# daughter.net
KiCad netlist of a schematic drawn in Altium Designer
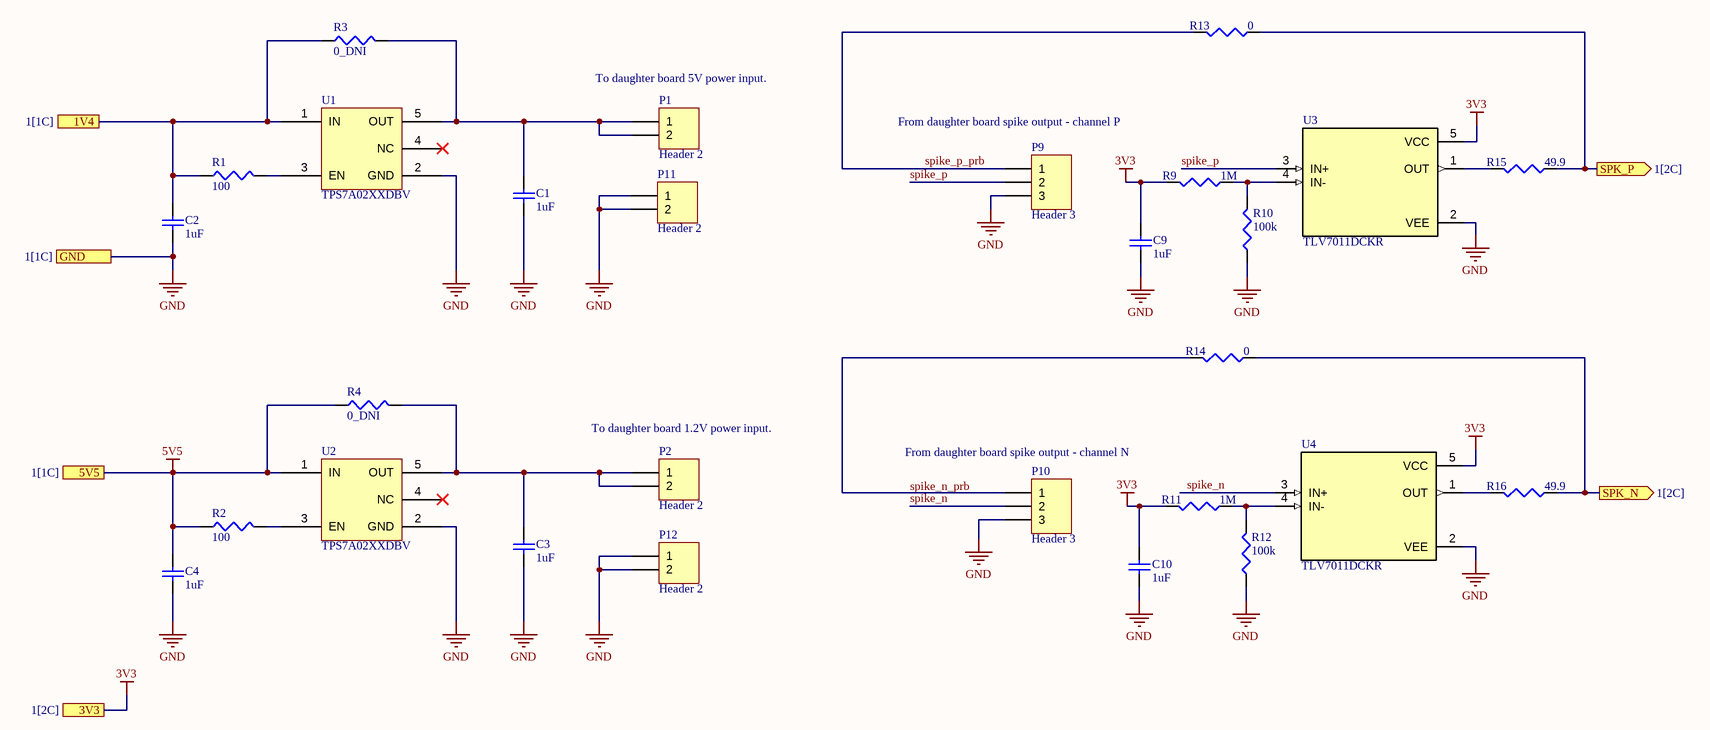
[diagram p0: daughter.SchDoc]

(export (version "E")
  (design (tool "Eeschema 10.0.6"))
  (components
    (comp (ref "C1")
      (value "1uF")
      (footprint "SMD-0603")
      (description "Ceramic Capacitor 0603")
      (libsource (lib "LCR") (part "CAP0603"))
    )
    (comp (ref "C2")
      (value "1uF")
      (footprint "SMD-0603")
      (description "Ceramic Capacitor 0603")
      (libsource (lib "LCR") (part "CAP0603"))
    )
    (comp (ref "C3")
      (value "1uF")
      (footprint "SMD-0603")
      (description "Ceramic Capacitor 0603")
      (libsource (lib "LCR") (part "CAP0603"))
    )
    (comp (ref "C4")
      (value "1uF")
      (footprint "SMD-0603")
      (description "Ceramic Capacitor 0603")
      (libsource (lib "LCR") (part "CAP0603"))
    )
    (comp (ref "C9")
      (value "1uF")
      (footprint "SMD-0603")
      (description "Ceramic Capacitor 0603")
      (libsource (lib "LCR") (part "CAP0603"))
    )
    (comp (ref "C10")
      (value "1uF")
      (footprint "SMD-0603")
      (description "Ceramic Capacitor 0603")
      (libsource (lib "LCR") (part "CAP0603"))
    )
    (comp (ref "P1")
      (value "Header 2")
      (footprint "HDR1X2")
      (description "Header, 2-Pin")
      (fields (field (name "PUBLISHER") "Altium Limited"))
      (libsource (lib "Miscellaneous Connectors") (part "Header 2"))
    )
    (comp (ref "P2")
      (value "Header 2")
      (footprint "HDR1X2")
      (description "Header, 2-Pin")
      (fields (field (name "PUBLISHER") "Altium Limited"))
      (libsource (lib "Miscellaneous Connectors") (part "Header 2"))
    )
    (comp (ref "P9")
      (value "Header 3")
      (footprint "HDR1X3")
      (description "Header, 3-Pin")
      (fields (field (name "PUBLISHER") "Altium Limited"))
      (libsource (lib "Miscellaneous Connectors") (part "Header 3"))
    )
    (comp (ref "P10")
      (value "Header 3")
      (footprint "HDR1X3")
      (description "Header, 3-Pin")
      (fields (field (name "PUBLISHER") "Altium Limited"))
      (libsource (lib "Miscellaneous Connectors") (part "Header 3"))
    )
    (comp (ref "P11")
      (value "Header 2")
      (footprint "HDR1X2")
      (description "Header, 2-Pin")
      (fields (field (name "PUBLISHER") "Altium Limited"))
      (libsource (lib "Miscellaneous Connectors") (part "Header 2"))
    )
    (comp (ref "P12")
      (value "Header 2")
      (footprint "HDR1X2")
      (description "Header, 2-Pin")
      (fields (field (name "PUBLISHER") "Altium Limited"))
      (libsource (lib "Miscellaneous Connectors") (part "Header 2"))
    )
    (comp (ref "R1")
      (value "100")
      (footprint "SMD-0603")
      (description "Resistor-0603")
      (libsource (lib "LCR") (part "RES0603"))
    )
    (comp (ref "R2")
      (value "100")
      (footprint "SMD-0603")
      (description "Resistor-0603")
      (libsource (lib "LCR") (part "RES0603"))
    )
    (comp (ref "R3")
      (value "0_DNI")
      (footprint "SMD-0603")
      (description "Resistor-0603")
      (libsource (lib "LCR") (part "RES0603"))
    )
    (comp (ref "R4")
      (value "0_DNI")
      (footprint "SMD-0603")
      (description "Resistor-0603")
      (libsource (lib "LCR") (part "RES0603"))
    )
    (comp (ref "R9")
      (value "1M")
      (footprint "SMD-0603")
      (description "Resistor-0603")
      (libsource (lib "LCR") (part "RES0603"))
    )
    (comp (ref "R10")
      (value "100k")
      (footprint "SMD-0603")
      (description "Resistor-0603")
      (libsource (lib "LCR") (part "RES0603"))
    )
    (comp (ref "R11")
      (value "1M")
      (footprint "SMD-0603")
      (description "Resistor-0603")
      (libsource (lib "LCR") (part "RES0603"))
    )
    (comp (ref "R12")
      (value "100k")
      (footprint "SMD-0603")
      (description "Resistor-0603")
      (libsource (lib "LCR") (part "RES0603"))
    )
    (comp (ref "R13")
      (value "0")
      (footprint "SMD-0603")
      (description "Resistor-0603")
      (libsource (lib "LCR") (part "RES0603"))
    )
    (comp (ref "R14")
      (value "0")
      (footprint "SMD-0603")
      (description "Resistor-0603")
      (libsource (lib "LCR") (part "RES0603"))
    )
    (comp (ref "R15")
      (value "49.9")
      (footprint "SMD-0603")
      (description "Resistor-0603")
      (libsource (lib "LCR") (part "RES0603"))
    )
    (comp (ref "R16")
      (value "49.9")
      (footprint "SMD-0603")
      (description "Resistor-0603")
      (libsource (lib "LCR") (part "RES0603"))
    )
    (comp (ref "U1")
      (value "TPS7A02XXDBV")
      (footprint "SOT95P280X145-5N")
      (description "TPS7A02 Nanopower IQ, 25-nA, 200-mA, Low-Dropout Voltage Regulator With Fast\r\nTransient Response")
      (libsource (lib "PowerManagement") (part "TPS7A02XXDBV"))
    )
    (comp (ref "U2")
      (value "TPS7A02XXDBV")
      (footprint "SOT95P280X145-5N")
      (description "TPS7A02 Nanopower IQ, 25-nA, 200-mA, Low-Dropout Voltage Regulator With Fast\r\nTransient Response")
      (libsource (lib "PowerManagement") (part "TPS7A02XXDBV"))
    )
    (comp (ref "U3")
      (value "TLV7011DCKR")
      (footprint "SOT65P210X110-5N")
      (description "Low power, small size comparator with push-pull output")
      (fields (field (name "MF") "Texas Instruments"))
      (libsource (lib "TLV7011DCKR") (part "TLV7011DCKR"))
    )
    (comp (ref "U4")
      (value "TLV7011DCKR")
      (footprint "SOT65P210X110-5N")
      (description "Low power, small size comparator with push-pull output")
      (fields (field (name "MF") "Texas Instruments"))
      (libsource (lib "TLV7011DCKR") (part "TLV7011DCKR"))
    )
  )
  (nets
    (net (code "1") (name "/1V4") (class "Default")
      (node (ref "C2") (pin "2") (pinfunction "2_2") (pintype "passive"))
      (node (ref "R1") (pin "1") (pinfunction "1_1") (pintype "passive"))
      (node (ref "R3") (pin "1") (pinfunction "1_1") (pintype "passive"))
      (node (ref "U1") (pin "1") (pinfunction "IN_1") (pintype "passive"))
    )
    (net (code "2") (name "/SPK_N") (class "Default")
      (node (ref "R14") (pin "1") (pinfunction "1_1") (pintype "passive"))
      (node (ref "R16") (pin "1") (pinfunction "1_1") (pintype "passive"))
    )
    (net (code "3") (name "/SPK_P") (class "Default")
      (node (ref "R13") (pin "1") (pinfunction "1_1") (pintype "passive"))
      (node (ref "R15") (pin "1") (pinfunction "1_1") (pintype "passive"))
    )
    (net (code "4") (name "/spike_n") (class "Default")
      (node (ref "P10") (pin "2") (pinfunction "2_2") (pintype "passive"))
      (node (ref "U4") (pin "3") (pinfunction "IN+_3") (pintype "input"))
    )
    (net (code "6") (name "/spike_p") (class "Default")
      (node (ref "P9") (pin "2") (pinfunction "2_2") (pintype "passive"))
      (node (ref "U3") (pin "3") (pinfunction "IN+_3") (pintype "input"))
    )
    (net (code "7") (name "/spike_p_prb") (class "Default")
      (node (ref "P9") (pin "1") (pinfunction "1_1") (pintype "passive"))
      (node (ref "R13") (pin "2") (pinfunction "2_2") (pintype "passive"))
    )
    (net (code "8") (name "3V3") (class "Default")
      (node (ref "C10") (pin "2") (pinfunction "2_2") (pintype "passive"))
      (node (ref "C9") (pin "2") (pinfunction "2_2") (pintype "passive"))
      (node (ref "R11") (pin "2") (pinfunction "2_2") (pintype "passive"))
      (node (ref "R9") (pin "2") (pinfunction "2_2") (pintype "passive"))
      (node (ref "U3") (pin "5") (pinfunction "VCC_5") (pintype "power_in"))
      (node (ref "U4") (pin "5") (pinfunction "VCC_5") (pintype "power_in"))
    )
    (net (code "9") (name "5V5") (class "Default")
      (node (ref "C4") (pin "2") (pinfunction "2_2") (pintype "passive"))
      (node (ref "R2") (pin "1") (pinfunction "1_1") (pintype "passive"))
      (node (ref "R4") (pin "1") (pinfunction "1_1") (pintype "passive"))
      (node (ref "U2") (pin "1") (pinfunction "IN_1") (pintype "passive"))
    )
    (net (code "10") (name "GND") (class "Default")
      (node (ref "C1") (pin "1") (pinfunction "1_1") (pintype "passive"))
      (node (ref "C10") (pin "1") (pinfunction "1_1") (pintype "passive"))
      (node (ref "C2") (pin "1") (pinfunction "1_1") (pintype "passive"))
      (node (ref "C3") (pin "1") (pinfunction "1_1") (pintype "passive"))
      (node (ref "C4") (pin "1") (pinfunction "1_1") (pintype "passive"))
      (node (ref "C9") (pin "1") (pinfunction "1_1") (pintype "passive"))
      (node (ref "P10") (pin "3") (pinfunction "3_3") (pintype "passive"))
      (node (ref "P11") (pin "1") (pinfunction "1_1") (pintype "passive"))
      (node (ref "P11") (pin "2") (pinfunction "2_2") (pintype "passive"))
      (node (ref "P12") (pin "1") (pinfunction "1_1") (pintype "passive"))
      (node (ref "P12") (pin "2") (pinfunction "2_2") (pintype "passive"))
      (node (ref "P9") (pin "3") (pinfunction "3_3") (pintype "passive"))
      (node (ref "R10") (pin "1") (pinfunction "1_1") (pintype "passive"))
      (node (ref "R12") (pin "1") (pinfunction "1_1") (pintype "passive"))
      (node (ref "U1") (pin "2") (pinfunction "GND_2") (pintype "passive"))
      (node (ref "U2") (pin "2") (pinfunction "GND_2") (pintype "passive"))
      (node (ref "U3") (pin "2") (pinfunction "VEE_2") (pintype "power_in"))
      (node (ref "U4") (pin "2") (pinfunction "VEE_2") (pintype "power_in"))
    )
    (net (code "11") (name "Net-(P10-Pad1)") (class "Default")
      (node (ref "P10") (pin "1") (pinfunction "1_1") (pintype "passive"))
      (node (ref "R14") (pin "2") (pinfunction "2_2") (pintype "passive"))
    )
    (net (code "12") (name "Net-(U1-EN)") (class "Default")
      (node (ref "R1") (pin "2") (pinfunction "2_2") (pintype "passive"))
      (node (ref "U1") (pin "3") (pinfunction "EN_3") (pintype "passive"))
    )
    (net (code "13") (name "Net-(U1-OUT)") (class "Default")
      (node (ref "C1") (pin "2") (pinfunction "2_2") (pintype "passive"))
      (node (ref "P1") (pin "1") (pinfunction "1_1") (pintype "passive"))
      (node (ref "P1") (pin "2") (pinfunction "2_2") (pintype "passive"))
      (node (ref "R3") (pin "2") (pinfunction "2_2") (pintype "passive"))
      (node (ref "U1") (pin "5") (pinfunction "OUT_5") (pintype "passive"))
    )
    (net (code "14") (name "Net-(U2-EN)") (class "Default")
      (node (ref "R2") (pin "2") (pinfunction "2_2") (pintype "passive"))
      (node (ref "U2") (pin "3") (pinfunction "EN_3") (pintype "passive"))
    )
    (net (code "15") (name "Net-(U2-OUT)") (class "Default")
      (node (ref "C3") (pin "2") (pinfunction "2_2") (pintype "passive"))
      (node (ref "P2") (pin "1") (pinfunction "1_1") (pintype "passive"))
      (node (ref "P2") (pin "2") (pinfunction "2_2") (pintype "passive"))
      (node (ref "R4") (pin "2") (pinfunction "2_2") (pintype "passive"))
      (node (ref "U2") (pin "5") (pinfunction "OUT_5") (pintype "passive"))
    )
    (net (code "16") (name "Net-(U3-IN-)") (class "Default")
      (node (ref "R10") (pin "2") (pinfunction "2_2") (pintype "passive"))
      (node (ref "R9") (pin "1") (pinfunction "1_1") (pintype "passive"))
      (node (ref "U3") (pin "4") (pinfunction "IN-_4") (pintype "input"))
    )
    (net (code "17") (name "Net-(U3-OUT)") (class "Default")
      (node (ref "R15") (pin "2") (pinfunction "2_2") (pintype "passive"))
      (node (ref "U3") (pin "1") (pinfunction "OUT_1") (pintype "output"))
    )
    (net (code "18") (name "Net-(U4-IN-)") (class "Default")
      (node (ref "R11") (pin "1") (pinfunction "1_1") (pintype "passive"))
      (node (ref "R12") (pin "2") (pinfunction "2_2") (pintype "passive"))
      (node (ref "U4") (pin "4") (pinfunction "IN-_4") (pintype "input"))
    )
    (net (code "19") (name "Net-(U4-OUT)") (class "Default")
      (node (ref "R16") (pin "2") (pinfunction "2_2") (pintype "passive"))
      (node (ref "U4") (pin "1") (pinfunction "OUT_1") (pintype "output"))
    )
    (net (code "20") (name "unconnected-(U1-NC-Pad4)") (class "Default")
      (node (ref "U1") (pin "4") (pinfunction "NC_4") (pintype "passive+no_connect"))
    )
    (net (code "21") (name "unconnected-(U2-NC-Pad4)") (class "Default")
      (node (ref "U2") (pin "4") (pinfunction "NC_4") (pintype "passive+no_connect"))
    )
  )
)
